# SCH_esp-firework-firing-system-v2_1.net
KiCad netlist of a schematic drawn in EasyEDA
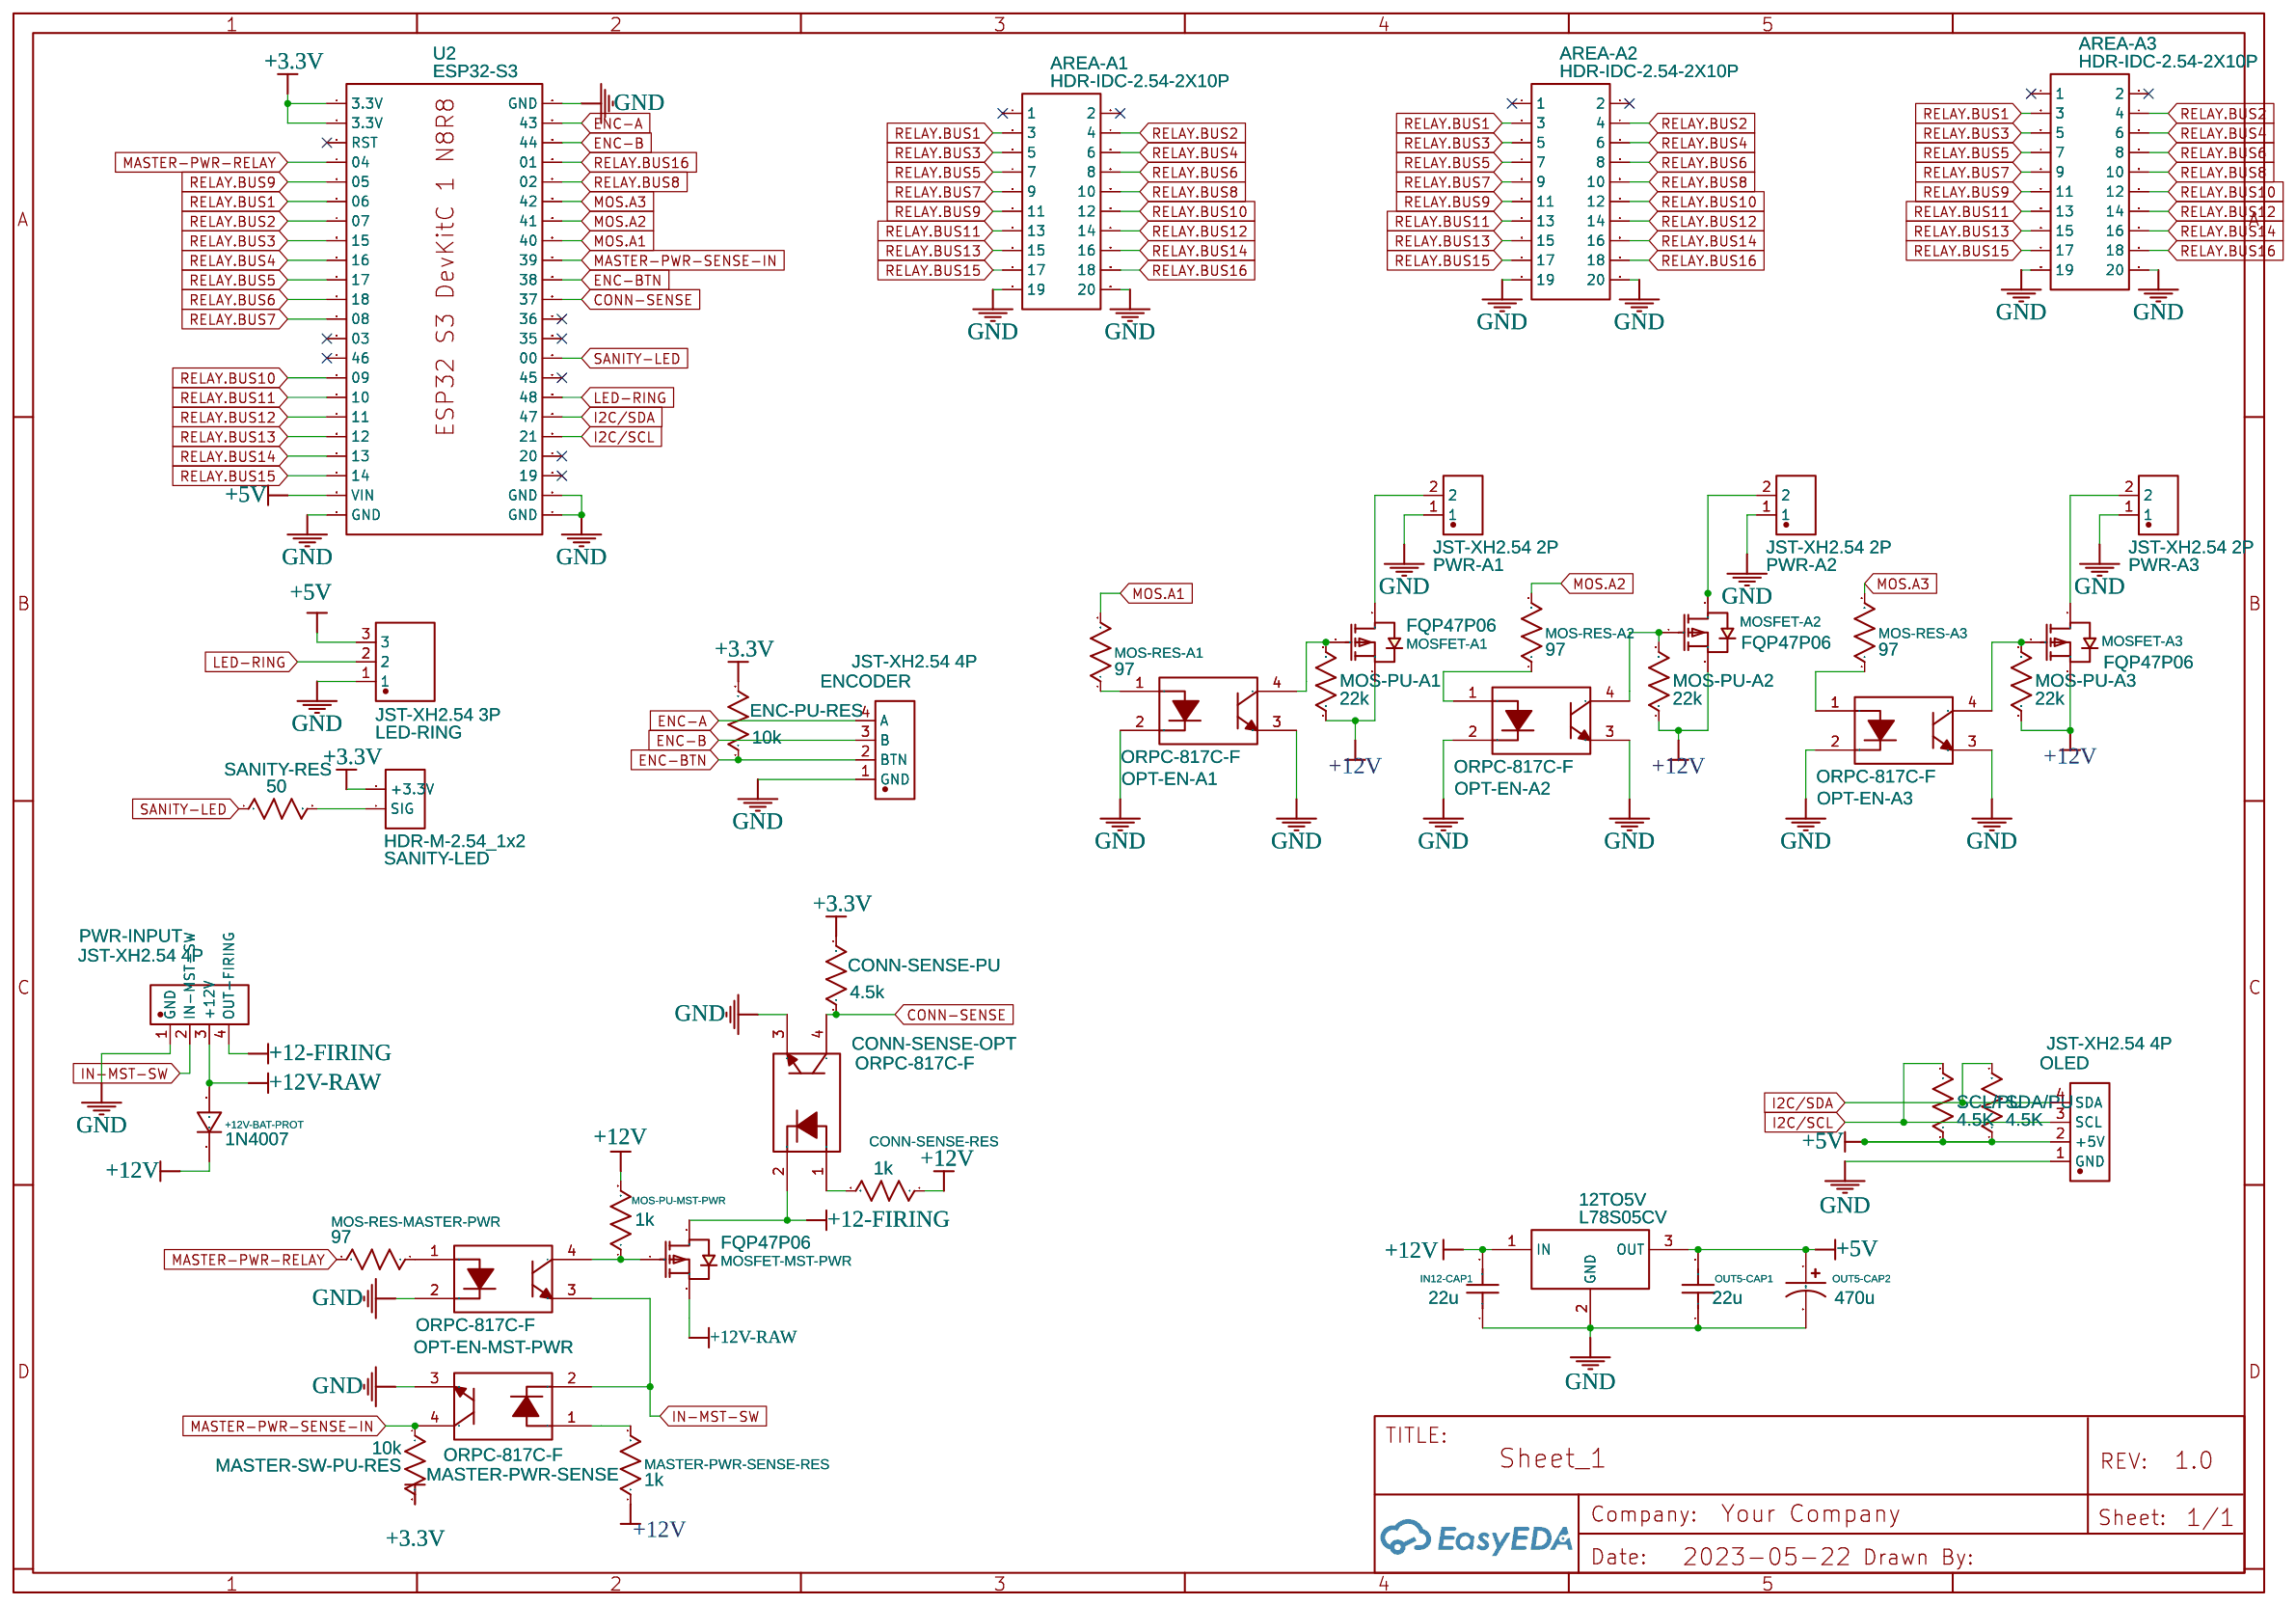
[diagram p0: schematic sheet]

(export (version "E")
  (design (tool "Eeschema 10.0.6"))
  (components
    (comp (ref "+12V-BAT-PROT")
      (value "1N4007")
      (fields (field (name "BOM_Supplier Part") "C106903"))
      (libsource (lib "") (part "1N4007"))
    )
    (comp (ref "12TO5V")
      (value "L78S05CV")
      (fields (field (name "BOM_Supplier Part") "C33043"))
      (libsource (lib "") (part "L78S05CV"))
    )
    (comp (ref "AREA-A1")
      (value "HDR-IDC-2.54-2X10P")
      (fields
        (field (name "BOM_Manufacturer Part") "IDC Box 2.54mm 2X10P　Straight")
        (field (name "BOM_Supplier Part") "C3405")
      )
      (libsource (lib "") (part "HDR-IDC-2.54-2X10P"))
    )
    (comp (ref "AREA-A2")
      (value "HDR-IDC-2.54-2X10P")
      (fields
        (field (name "BOM_Manufacturer Part") "IDC Box 2.54mm 2X10P　Straight")
        (field (name "BOM_Supplier Part") "C3405")
      )
      (libsource (lib "") (part "HDR-IDC-2.54-2X10P"))
    )
    (comp (ref "AREA-A3")
      (value "HDR-IDC-2.54-2X10P")
      (fields
        (field (name "BOM_Manufacturer Part") "IDC Box 2.54mm 2X10P　Straight")
        (field (name "BOM_Supplier Part") "C3405")
      )
      (libsource (lib "") (part "HDR-IDC-2.54-2X10P"))
    )
    (comp (ref "CONN-SENSE-OPT")
      (value "ORPC-817C-F")
      (fields (field (name "BOM_Supplier Part") "C2842770"))
      (libsource (lib "") (part "ORPC-817C-F_3"))
    )
    (comp (ref "CONN-SENSE-PU") (value "4.5k") (libsource (lib "") (part "R_AXIAL-0.3_US_6")))
    (comp (ref "CONN-SENSE-RES") (value "1k") (libsource (lib "") (part "R_AXIAL-0.3_US_11")))
    (comp (ref "ENC-PU-RES") (value "10k") (libsource (lib "") (part "R_AXIAL-0.3_US_1")))
    (comp (ref "ENCODER") (value "JST-XH2.54 4P") (libsource (lib "") (part "JST-XH2.54 4P")))
    (comp (ref "IN12-CAP1") (value "22u") (libsource (lib "") (part "C_RAD-0.1_US_1")))
    (comp (ref "LED-RING") (value "JST-XH2.54 3P") (libsource (lib "") (part "JST-XH2.54 3P")))
    (comp (ref "MASTER-PWR-SENSE")
      (value "ORPC-817C-F")
      (fields (field (name "BOM_Supplier Part") "C2842770"))
      (libsource (lib "") (part "ORPC-817C-F_2"))
    )
    (comp (ref "MASTER-PWR-SENSE-RES") (value "1k") (libsource (lib "") (part "R_AXIAL-0.3_US_7")))
    (comp (ref "MASTER-SW-PU-RES") (value "10k") (libsource (lib "") (part "R_AXIAL-0.3_US_4")))
    (comp (ref "MOS-PU-A1") (value "22k") (libsource (lib "") (part "R_AXIAL-0.3_US_2")))
    (comp (ref "MOS-PU-A2") (value "22k") (libsource (lib "") (part "R_AXIAL-0.3_US_2")))
    (comp (ref "MOS-PU-A3") (value "22k") (libsource (lib "") (part "R_AXIAL-0.3_US_2")))
    (comp (ref "MOS-PU-MST-PWR") (value "1k") (libsource (lib "") (part "R_AXIAL-0.3_US_5")))
    (comp (ref "MOS-RES-A1") (value "97") (libsource (lib "") (part "R_AXIAL-0.3_US")))
    (comp (ref "MOS-RES-A2") (value "97") (libsource (lib "") (part "R_AXIAL-0.3_US")))
    (comp (ref "MOS-RES-A3") (value "97") (libsource (lib "") (part "R_AXIAL-0.3_US")))
    (comp (ref "MOS-RES-MASTER-PWR") (value "97") (libsource (lib "") (part "R_AXIAL-0.3_US_10")))
    (comp (ref "MOSFET-A1")
      (value "FQP47P06")
      (fields (field (name "BOM_Supplier Part") "C462765"))
      (libsource (lib "") (part "FQP47P06"))
    )
    (comp (ref "MOSFET-A2")
      (value "FQP47P06")
      (fields (field (name "BOM_Supplier Part") "C462765"))
      (libsource (lib "") (part "FQP47P06"))
    )
    (comp (ref "MOSFET-A3")
      (value "FQP47P06")
      (fields (field (name "BOM_Supplier Part") "C462765"))
      (libsource (lib "") (part "FQP47P06"))
    )
    (comp (ref "MOSFET-MST-PWR")
      (value "FQP47P06")
      (fields (field (name "BOM_Supplier Part") "C462765"))
      (libsource (lib "") (part "FQP47P06_1"))
    )
    (comp (ref "OLED") (value "JST-XH2.54 4P") (libsource (lib "") (part "JST-XH2.54 4P_1")))
    (comp (ref "OPT-EN-A1")
      (value "ORPC-817C-F")
      (fields (field (name "BOM_Supplier Part") "C2842770"))
      (libsource (lib "") (part "ORPC-817C-F"))
    )
    (comp (ref "OPT-EN-A2")
      (value "ORPC-817C-F")
      (fields (field (name "BOM_Supplier Part") "C2842770"))
      (libsource (lib "") (part "ORPC-817C-F"))
    )
    (comp (ref "OPT-EN-A3")
      (value "ORPC-817C-F")
      (fields (field (name "BOM_Supplier Part") "C2842770"))
      (libsource (lib "") (part "ORPC-817C-F"))
    )
    (comp (ref "OPT-EN-MST-PWR")
      (value "ORPC-817C-F")
      (fields (field (name "BOM_Supplier Part") "C2842770"))
      (libsource (lib "") (part "ORPC-817C-F_1"))
    )
    (comp (ref "OUT5-CAP1") (value "22u") (libsource (lib "") (part "C_RAD-0.1_US")))
    (comp (ref "OUT5-CAP2") (value "470u") (libsource (lib "") (part "CE_TH_D6.3×F2.5_US")))
    (comp (ref "PWR-A1") (value "JST-XH2.54 2P") (libsource (lib "") (part "JST-XH2.54 2P")))
    (comp (ref "PWR-A2") (value "JST-XH2.54 2P") (libsource (lib "") (part "JST-XH2.54 2P")))
    (comp (ref "PWR-A3") (value "JST-XH2.54 2P") (libsource (lib "") (part "JST-XH2.54 2P")))
    (comp (ref "PWR-INPUT") (value "JST-XH2.54 4P") (libsource (lib "") (part "JST-XH2.54 4P_2")))
    (comp (ref "SANITY-LED")
      (value "HDR-M-2.54_1x2")
      (fields (field (name "BOM_Supplier Part") "C124375"))
      (libsource (lib "") (part "HDR-M-2.54_1x2"))
    )
    (comp (ref "SANITY-RES") (value "50") (libsource (lib "") (part "R_AXIAL-0.3_US_9")))
    (comp (ref "SCL/PU") (value "4.5K") (libsource (lib "") (part "R_AXIAL-0.3_US_8")))
    (comp (ref "SDA/PU") (value "4.5K") (libsource (lib "") (part "R_AXIAL-0.3_US_3")))
    (comp (ref "U2") (value "ESP32-S3") (libsource (lib "") (part "ESP32-S3")))
  )
  (nets
    (net (code "1") (name "+3.3V") (class "Default")
      (node (ref "CONN-SENSE-PU") (pin "2") (pinfunction "2_2") (pintype "unspecified"))
      (node (ref "ENC-PU-RES") (pin "2") (pinfunction "2_2") (pintype "unspecified"))
      (node (ref "MASTER-SW-PU-RES") (pin "2") (pinfunction "2_2") (pintype "unspecified"))
      (node (ref "SANITY-LED") (pin "2") (pinfunction "+3.3V_2") (pintype "unspecified"))
      (node (ref "U2") (pin "1") (pinfunction "3.3V_1") (pintype "unspecified"))
      (node (ref "U2") (pin "2") (pinfunction "3.3V_2") (pintype "unspecified"))
    )
    (net (code "2") (name "+5V") (class "Default")
      (node (ref "12TO5V") (pin "3") (pinfunction "OUT_3") (pintype "passive"))
      (node (ref "LED-RING") (pin "3") (pinfunction "3_3") (pintype "unspecified"))
      (node (ref "OLED") (pin "2") (pinfunction "+5V_2") (pintype "unspecified"))
      (node (ref "OUT5-CAP1") (pin "2") (pinfunction "2_2") (pintype "unspecified"))
      (node (ref "OUT5-CAP2") (pin "1") (pinfunction "1_1") (pintype "unspecified"))
      (node (ref "SCL/PU") (pin "1") (pinfunction "1_1") (pintype "unspecified"))
      (node (ref "SDA/PU") (pin "1") (pinfunction "1_1") (pintype "unspecified"))
      (node (ref "U2") (pin "21") (pinfunction "VIN_21") (pintype "unspecified"))
    )
    (net (code "3") (name "+12-FIRING") (class "Default")
      (node (ref "CONN-SENSE-OPT") (pin "2") (pinfunction "2_2") (pintype "unspecified"))
      (node (ref "MOSFET-MST-PWR") (pin "2") (pinfunction "D_2") (pintype "unspecified"))
      (node (ref "PWR-INPUT") (pin "4") (pinfunction "OUT-FIRING_4") (pintype "unspecified"))
    )
    (net (code "4") (name "+12V") (class "Default")
      (node (ref "+12V-BAT-PROT") (pin "1") (pinfunction "1_1") (pintype "unspecified"))
      (node (ref "12TO5V") (pin "1") (pinfunction "IN_1") (pintype "passive"))
      (node (ref "CONN-SENSE-RES") (pin "1") (pinfunction "1_1") (pintype "unspecified"))
      (node (ref "IN12-CAP1") (pin "2") (pinfunction "2_2") (pintype "unspecified"))
      (node (ref "MASTER-PWR-SENSE-RES") (pin "1") (pinfunction "1_1") (pintype "unspecified"))
      (node (ref "MOS-PU-A1") (pin "1") (pinfunction "1_1") (pintype "unspecified"))
      (node (ref "MOS-PU-A2") (pin "1") (pinfunction "1_1") (pintype "unspecified"))
      (node (ref "MOS-PU-A3") (pin "1") (pinfunction "1_1") (pintype "unspecified"))
      (node (ref "MOS-PU-MST-PWR") (pin "2") (pinfunction "2_2") (pintype "unspecified"))
      (node (ref "MOSFET-A1") (pin "3") (pinfunction "S_3") (pintype "unspecified"))
      (node (ref "MOSFET-A2") (pin "3") (pinfunction "S_3") (pintype "unspecified"))
      (node (ref "MOSFET-A3") (pin "3") (pinfunction "S_3") (pintype "unspecified"))
    )
    (net (code "5") (name "+12V-RAW") (class "Default")
      (node (ref "+12V-BAT-PROT") (pin "2") (pinfunction "2_2") (pintype "unspecified"))
      (node (ref "MOSFET-MST-PWR") (pin "3") (pinfunction "S_3") (pintype "unspecified"))
      (node (ref "PWR-INPUT") (pin "3") (pinfunction "+12V_3") (pintype "unspecified"))
    )
    (net (code "6") (name "CONN-SENSE") (class "Default")
      (node (ref "CONN-SENSE-OPT") (pin "4") (pinfunction "4_4") (pintype "unspecified"))
      (node (ref "CONN-SENSE-PU") (pin "1") (pinfunction "1_1") (pintype "unspecified"))
      (node (ref "U2") (pin "33") (pinfunction "37_33") (pintype "unspecified"))
    )
    (net (code "7") (name "ENC-A") (class "Default")
      (node (ref "ENCODER") (pin "4") (pinfunction "A_4") (pintype "unspecified"))
      (node (ref "U2") (pin "24") (pinfunction "43_24") (pintype "unspecified"))
    )
    (net (code "8") (name "ENC-B") (class "Default")
      (node (ref "ENCODER") (pin "3") (pinfunction "B_3") (pintype "unspecified"))
      (node (ref "U2") (pin "25") (pinfunction "44_25") (pintype "unspecified"))
    )
    (net (code "9") (name "ENC-BTN") (class "Default")
      (node (ref "ENC-PU-RES") (pin "1") (pinfunction "1_1") (pintype "unspecified"))
      (node (ref "ENCODER") (pin "2") (pinfunction "BTN_2") (pintype "unspecified"))
      (node (ref "U2") (pin "32") (pinfunction "38_32") (pintype "unspecified"))
    )
    (net (code "10") (name "GND") (class "Default")
      (node (ref "12TO5V") (pin "2") (pinfunction "GND_2") (pintype "passive"))
      (node (ref "AREA-A1") (pin "19") (pinfunction "19_19") (pintype "unspecified"))
      (node (ref "AREA-A1") (pin "20") (pinfunction "20_20") (pintype "unspecified"))
      (node (ref "AREA-A2") (pin "19") (pinfunction "19_19") (pintype "unspecified"))
      (node (ref "AREA-A2") (pin "20") (pinfunction "20_20") (pintype "unspecified"))
      (node (ref "AREA-A3") (pin "19") (pinfunction "19_19") (pintype "unspecified"))
      (node (ref "AREA-A3") (pin "20") (pinfunction "20_20") (pintype "unspecified"))
      (node (ref "CONN-SENSE-OPT") (pin "3") (pinfunction "3_3") (pintype "unspecified"))
      (node (ref "ENCODER") (pin "1") (pinfunction "GND_1") (pintype "unspecified"))
      (node (ref "IN12-CAP1") (pin "1") (pinfunction "1_1") (pintype "unspecified"))
      (node (ref "LED-RING") (pin "1") (pinfunction "1_1") (pintype "unspecified"))
      (node (ref "MASTER-PWR-SENSE") (pin "3") (pinfunction "3_3") (pintype "unspecified"))
      (node (ref "OLED") (pin "1") (pinfunction "GND_1") (pintype "unspecified"))
      (node (ref "OPT-EN-A1") (pin "2") (pinfunction "2_2") (pintype "unspecified"))
      (node (ref "OPT-EN-A1") (pin "3") (pinfunction "3_3") (pintype "unspecified"))
      (node (ref "OPT-EN-A2") (pin "2") (pinfunction "2_2") (pintype "unspecified"))
      (node (ref "OPT-EN-A2") (pin "3") (pinfunction "3_3") (pintype "unspecified"))
      (node (ref "OPT-EN-A3") (pin "2") (pinfunction "2_2") (pintype "unspecified"))
      (node (ref "OPT-EN-A3") (pin "3") (pinfunction "3_3") (pintype "unspecified"))
      (node (ref "OPT-EN-MST-PWR") (pin "2") (pinfunction "2_2") (pintype "unspecified"))
      (node (ref "OUT5-CAP1") (pin "1") (pinfunction "1_1") (pintype "unspecified"))
      (node (ref "OUT5-CAP2") (pin "2") (pinfunction "2_2") (pintype "unspecified"))
      (node (ref "PWR-A1") (pin "1") (pinfunction "1_1") (pintype "unspecified"))
      (node (ref "PWR-A2") (pin "1") (pinfunction "1_1") (pintype "unspecified"))
      (node (ref "PWR-A3") (pin "1") (pinfunction "1_1") (pintype "unspecified"))
      (node (ref "PWR-INPUT") (pin "1") (pinfunction "GND_1") (pintype "unspecified"))
      (node (ref "U2") (pin "22") (pinfunction "GND_22") (pintype "unspecified"))
      (node (ref "U2") (pin "23") (pinfunction "GND_23") (pintype "unspecified"))
      (node (ref "U2") (pin "43") (pinfunction "GND_43") (pintype "unspecified"))
      (node (ref "U2") (pin "44") (pinfunction "GND_44") (pintype "unspecified"))
    )
    (net (code "11") (name "I2C{slash}SCL") (class "Default")
      (node (ref "OLED") (pin "3") (pinfunction "SCL_3") (pintype "unspecified"))
      (node (ref "SCL/PU") (pin "2") (pinfunction "2_2") (pintype "unspecified"))
      (node (ref "U2") (pin "40") (pinfunction "21_40") (pintype "unspecified"))
    )
    (net (code "12") (name "I2C{slash}SDA") (class "Default")
      (node (ref "OLED") (pin "4") (pinfunction "SDA_4") (pintype "unspecified"))
      (node (ref "SDA/PU") (pin "2") (pinfunction "2_2") (pintype "unspecified"))
      (node (ref "U2") (pin "39") (pinfunction "47_39") (pintype "unspecified"))
    )
    (net (code "13") (name "IN-MST-SW") (class "Default")
      (node (ref "MASTER-PWR-SENSE") (pin "2") (pinfunction "2_2") (pintype "unspecified"))
      (node (ref "OPT-EN-MST-PWR") (pin "3") (pinfunction "3_3") (pintype "unspecified"))
      (node (ref "PWR-INPUT") (pin "2") (pinfunction "IN-MST-SW_2") (pintype "unspecified"))
    )
    (net (code "14") (name "LED-RING") (class "Default")
      (node (ref "LED-RING") (pin "2") (pinfunction "2_2") (pintype "unspecified"))
      (node (ref "U2") (pin "38") (pinfunction "48_38") (pintype "unspecified"))
    )
    (net (code "15") (name "MASTER-PWR-RELAY") (class "Default")
      (node (ref "MOS-RES-MASTER-PWR") (pin "2") (pinfunction "2_2") (pintype "unspecified"))
      (node (ref "U2") (pin "4") (pinfunction "04_4") (pintype "unspecified"))
    )
    (net (code "16") (name "MASTER-PWR-SENSE-IN") (class "Default")
      (node (ref "MASTER-PWR-SENSE") (pin "4") (pinfunction "4_4") (pintype "unspecified"))
      (node (ref "MASTER-SW-PU-RES") (pin "1") (pinfunction "1_1") (pintype "unspecified"))
      (node (ref "U2") (pin "31") (pinfunction "39_31") (pintype "unspecified"))
    )
    (net (code "17") (name "MOS.A1") (class "Default")
      (node (ref "MOS-RES-A1") (pin "2") (pinfunction "2_2") (pintype "unspecified"))
      (node (ref "U2") (pin "30") (pinfunction "40_30") (pintype "unspecified"))
    )
    (net (code "18") (name "MOS.A2") (class "Default")
      (node (ref "MOS-RES-A2") (pin "2") (pinfunction "2_2") (pintype "unspecified"))
      (node (ref "U2") (pin "29") (pinfunction "41_29") (pintype "unspecified"))
    )
    (net (code "19") (name "MOS.A3") (class "Default")
      (node (ref "MOS-RES-A3") (pin "2") (pinfunction "2_2") (pintype "unspecified"))
      (node (ref "U2") (pin "28") (pinfunction "42_28") (pintype "unspecified"))
    )
    (net (code "20") (name "Net-(CONN-SENSE-OPT-Pad1)") (class "Default")
      (node (ref "CONN-SENSE-OPT") (pin "1") (pinfunction "1_1") (pintype "unspecified"))
      (node (ref "CONN-SENSE-RES") (pin "2") (pinfunction "2_2") (pintype "unspecified"))
    )
    (net (code "21") (name "Net-(MASTER-PWR-SENSE-Pad1)") (class "Default")
      (node (ref "MASTER-PWR-SENSE") (pin "1") (pinfunction "1_1") (pintype "unspecified"))
      (node (ref "MASTER-PWR-SENSE-RES") (pin "2") (pinfunction "2_2") (pintype "unspecified"))
    )
    (net (code "22") (name "Net-(MOS-RES-A1-Pad1)") (class "Default")
      (node (ref "MOS-RES-A1") (pin "1") (pinfunction "1_1") (pintype "unspecified"))
      (node (ref "OPT-EN-A1") (pin "1") (pinfunction "1_1") (pintype "unspecified"))
    )
    (net (code "23") (name "Net-(MOS-RES-A2-Pad1)") (class "Default")
      (node (ref "MOS-RES-A2") (pin "1") (pinfunction "1_1") (pintype "unspecified"))
      (node (ref "OPT-EN-A2") (pin "1") (pinfunction "1_1") (pintype "unspecified"))
    )
    (net (code "24") (name "Net-(MOS-RES-A3-Pad1)") (class "Default")
      (node (ref "MOS-RES-A3") (pin "1") (pinfunction "1_1") (pintype "unspecified"))
      (node (ref "OPT-EN-A3") (pin "1") (pinfunction "1_1") (pintype "unspecified"))
    )
    (net (code "25") (name "Net-(MOS-RES-MASTER-PWR-Pad1)") (class "Default")
      (node (ref "MOS-RES-MASTER-PWR") (pin "1") (pinfunction "1_1") (pintype "unspecified"))
      (node (ref "OPT-EN-MST-PWR") (pin "1") (pinfunction "1_1") (pintype "unspecified"))
    )
    (net (code "26") (name "Net-(MOSFET-A1-D)") (class "Default")
      (node (ref "MOSFET-A1") (pin "2") (pinfunction "D_2") (pintype "unspecified"))
      (node (ref "PWR-A1") (pin "2") (pinfunction "2_2") (pintype "unspecified"))
    )
    (net (code "27") (name "Net-(MOSFET-A1-G)") (class "Default")
      (node (ref "MOS-PU-A1") (pin "2") (pinfunction "2_2") (pintype "unspecified"))
      (node (ref "MOSFET-A1") (pin "1") (pinfunction "G_1") (pintype "unspecified"))
      (node (ref "OPT-EN-A1") (pin "4") (pinfunction "4_4") (pintype "unspecified"))
    )
    (net (code "28") (name "Net-(MOSFET-A2-D)") (class "Default")
      (node (ref "MOSFET-A2") (pin "2") (pinfunction "D_2") (pintype "unspecified"))
      (node (ref "PWR-A2") (pin "2") (pinfunction "2_2") (pintype "unspecified"))
    )
    (net (code "29") (name "Net-(MOSFET-A2-G)") (class "Default")
      (node (ref "MOS-PU-A2") (pin "2") (pinfunction "2_2") (pintype "unspecified"))
      (node (ref "MOSFET-A2") (pin "1") (pinfunction "G_1") (pintype "unspecified"))
      (node (ref "OPT-EN-A2") (pin "4") (pinfunction "4_4") (pintype "unspecified"))
    )
    (net (code "30") (name "Net-(MOSFET-A3-D)") (class "Default")
      (node (ref "MOSFET-A3") (pin "2") (pinfunction "D_2") (pintype "unspecified"))
      (node (ref "PWR-A3") (pin "2") (pinfunction "2_2") (pintype "unspecified"))
    )
    (net (code "31") (name "Net-(MOSFET-A3-G)") (class "Default")
      (node (ref "MOS-PU-A3") (pin "2") (pinfunction "2_2") (pintype "unspecified"))
      (node (ref "MOSFET-A3") (pin "1") (pinfunction "G_1") (pintype "unspecified"))
      (node (ref "OPT-EN-A3") (pin "4") (pinfunction "4_4") (pintype "unspecified"))
    )
    (net (code "32") (name "Net-(MOSFET-MST-PWR-G)") (class "Default")
      (node (ref "MOS-PU-MST-PWR") (pin "1") (pinfunction "1_1") (pintype "unspecified"))
      (node (ref "MOSFET-MST-PWR") (pin "1") (pinfunction "G_1") (pintype "unspecified"))
      (node (ref "OPT-EN-MST-PWR") (pin "4") (pinfunction "4_4") (pintype "unspecified"))
    )
    (net (code "33") (name "Net-(SANITY-LED-SIG)") (class "Default")
      (node (ref "SANITY-LED") (pin "1") (pinfunction "SIG_1") (pintype "unspecified"))
      (node (ref "SANITY-RES") (pin "2") (pinfunction "2_2") (pintype "unspecified"))
    )
    (net (code "34") (name "RELAY.BUS1") (class "Default")
      (node (ref "AREA-A1") (pin "3") (pinfunction "3_3") (pintype "unspecified"))
      (node (ref "AREA-A2") (pin "3") (pinfunction "3_3") (pintype "unspecified"))
      (node (ref "AREA-A3") (pin "3") (pinfunction "3_3") (pintype "unspecified"))
      (node (ref "U2") (pin "6") (pinfunction "06_6") (pintype "unspecified"))
    )
    (net (code "35") (name "RELAY.BUS2") (class "Default")
      (node (ref "AREA-A1") (pin "4") (pinfunction "4_4") (pintype "unspecified"))
      (node (ref "AREA-A2") (pin "4") (pinfunction "4_4") (pintype "unspecified"))
      (node (ref "AREA-A3") (pin "4") (pinfunction "4_4") (pintype "unspecified"))
      (node (ref "U2") (pin "7") (pinfunction "07_7") (pintype "unspecified"))
    )
    (net (code "36") (name "RELAY.BUS3") (class "Default")
      (node (ref "AREA-A1") (pin "5") (pinfunction "5_5") (pintype "unspecified"))
      (node (ref "AREA-A2") (pin "5") (pinfunction "5_5") (pintype "unspecified"))
      (node (ref "AREA-A3") (pin "5") (pinfunction "5_5") (pintype "unspecified"))
      (node (ref "U2") (pin "8") (pinfunction "15_8") (pintype "unspecified"))
    )
    (net (code "37") (name "RELAY.BUS4") (class "Default")
      (node (ref "AREA-A1") (pin "6") (pinfunction "6_6") (pintype "unspecified"))
      (node (ref "AREA-A2") (pin "6") (pinfunction "6_6") (pintype "unspecified"))
      (node (ref "AREA-A3") (pin "6") (pinfunction "6_6") (pintype "unspecified"))
      (node (ref "U2") (pin "9") (pinfunction "16_9") (pintype "unspecified"))
    )
    (net (code "38") (name "RELAY.BUS5") (class "Default")
      (node (ref "AREA-A1") (pin "7") (pinfunction "7_7") (pintype "unspecified"))
      (node (ref "AREA-A2") (pin "7") (pinfunction "7_7") (pintype "unspecified"))
      (node (ref "AREA-A3") (pin "7") (pinfunction "7_7") (pintype "unspecified"))
      (node (ref "U2") (pin "10") (pinfunction "17_10") (pintype "unspecified"))
    )
    (net (code "39") (name "RELAY.BUS6") (class "Default")
      (node (ref "AREA-A1") (pin "8") (pinfunction "8_8") (pintype "unspecified"))
      (node (ref "AREA-A2") (pin "8") (pinfunction "8_8") (pintype "unspecified"))
      (node (ref "AREA-A3") (pin "8") (pinfunction "8_8") (pintype "unspecified"))
      (node (ref "U2") (pin "11") (pinfunction "18_11") (pintype "unspecified"))
    )
    (net (code "40") (name "RELAY.BUS7") (class "Default")
      (node (ref "AREA-A1") (pin "9") (pinfunction "9_9") (pintype "unspecified"))
      (node (ref "AREA-A2") (pin "9") (pinfunction "9_9") (pintype "unspecified"))
      (node (ref "AREA-A3") (pin "9") (pinfunction "9_9") (pintype "unspecified"))
      (node (ref "U2") (pin "12") (pinfunction "08_12") (pintype "unspecified"))
    )
    (net (code "41") (name "RELAY.BUS8") (class "Default")
      (node (ref "AREA-A1") (pin "10") (pinfunction "10_10") (pintype "unspecified"))
      (node (ref "AREA-A2") (pin "10") (pinfunction "10_10") (pintype "unspecified"))
      (node (ref "AREA-A3") (pin "10") (pinfunction "10_10") (pintype "unspecified"))
      (node (ref "U2") (pin "27") (pinfunction "02_27") (pintype "unspecified"))
    )
    (net (code "42") (name "RELAY.BUS9") (class "Default")
      (node (ref "AREA-A1") (pin "11") (pinfunction "11_11") (pintype "unspecified"))
      (node (ref "AREA-A2") (pin "11") (pinfunction "11_11") (pintype "unspecified"))
      (node (ref "AREA-A3") (pin "11") (pinfunction "11_11") (pintype "unspecified"))
      (node (ref "U2") (pin "5") (pinfunction "05_5") (pintype "unspecified"))
    )
    (net (code "43") (name "RELAY.BUS10") (class "Default")
      (node (ref "AREA-A1") (pin "12") (pinfunction "12_12") (pintype "unspecified"))
      (node (ref "AREA-A2") (pin "12") (pinfunction "12_12") (pintype "unspecified"))
      (node (ref "AREA-A3") (pin "12") (pinfunction "12_12") (pintype "unspecified"))
      (node (ref "U2") (pin "15") (pinfunction "09_15") (pintype "unspecified"))
    )
    (net (code "44") (name "RELAY.BUS11") (class "Default")
      (node (ref "AREA-A1") (pin "13") (pinfunction "13_13") (pintype "unspecified"))
      (node (ref "AREA-A2") (pin "13") (pinfunction "13_13") (pintype "unspecified"))
      (node (ref "AREA-A3") (pin "13") (pinfunction "13_13") (pintype "unspecified"))
      (node (ref "U2") (pin "16") (pinfunction "10_16") (pintype "unspecified"))
    )
    (net (code "45") (name "RELAY.BUS12") (class "Default")
      (node (ref "AREA-A1") (pin "14") (pinfunction "14_14") (pintype "unspecified"))
      (node (ref "AREA-A2") (pin "14") (pinfunction "14_14") (pintype "unspecified"))
      (node (ref "AREA-A3") (pin "14") (pinfunction "14_14") (pintype "unspecified"))
      (node (ref "U2") (pin "17") (pinfunction "11_17") (pintype "unspecified"))
    )
    (net (code "46") (name "RELAY.BUS13") (class "Default")
      (node (ref "AREA-A1") (pin "15") (pinfunction "15_15") (pintype "unspecified"))
      (node (ref "AREA-A2") (pin "15") (pinfunction "15_15") (pintype "unspecified"))
      (node (ref "AREA-A3") (pin "15") (pinfunction "15_15") (pintype "unspecified"))
      (node (ref "U2") (pin "18") (pinfunction "12_18") (pintype "unspecified"))
    )
    (net (code "47") (name "RELAY.BUS14") (class "Default")
      (node (ref "AREA-A1") (pin "16") (pinfunction "16_16") (pintype "unspecified"))
      (node (ref "AREA-A2") (pin "16") (pinfunction "16_16") (pintype "unspecified"))
      (node (ref "AREA-A3") (pin "16") (pinfunction "16_16") (pintype "unspecified"))
      (node (ref "U2") (pin "19") (pinfunction "13_19") (pintype "unspecified"))
    )
    (net (code "48") (name "RELAY.BUS15") (class "Default")
      (node (ref "AREA-A1") (pin "17") (pinfunction "17_17") (pintype "unspecified"))
      (node (ref "AREA-A2") (pin "17") (pinfunction "17_17") (pintype "unspecified"))
      (node (ref "AREA-A3") (pin "17") (pinfunction "17_17") (pintype "unspecified"))
      (node (ref "U2") (pin "20") (pinfunction "14_20") (pintype "unspecified"))
    )
    (net (code "49") (name "RELAY.BUS16") (class "Default")
      (node (ref "AREA-A1") (pin "18") (pinfunction "18_18") (pintype "unspecified"))
      (node (ref "AREA-A2") (pin "18") (pinfunction "18_18") (pintype "unspecified"))
      (node (ref "AREA-A3") (pin "18") (pinfunction "18_18") (pintype "unspecified"))
      (node (ref "U2") (pin "26") (pinfunction "01_26") (pintype "unspecified"))
    )
    (net (code "50") (name "SANITY-LED") (class "Default")
      (node (ref "SANITY-RES") (pin "1") (pinfunction "1_1") (pintype "unspecified"))
      (node (ref "U2") (pin "36") (pinfunction "00_36") (pintype "unspecified"))
    )
    (net (code "51") (name "unconnected-(AREA-A1-Pad1)") (class "Default")
      (node (ref "AREA-A1") (pin "1") (pinfunction "1_1") (pintype "unspecified+no_connect"))
    )
    (net (code "52") (name "unconnected-(AREA-A1-Pad2)") (class "Default")
      (node (ref "AREA-A1") (pin "2") (pinfunction "2_2") (pintype "unspecified+no_connect"))
    )
    (net (code "53") (name "unconnected-(AREA-A2-Pad1)") (class "Default")
      (node (ref "AREA-A2") (pin "1") (pinfunction "1_1") (pintype "unspecified+no_connect"))
    )
    (net (code "54") (name "unconnected-(AREA-A2-Pad2)") (class "Default")
      (node (ref "AREA-A2") (pin "2") (pinfunction "2_2") (pintype "unspecified+no_connect"))
    )
    (net (code "55") (name "unconnected-(AREA-A3-Pad1)") (class "Default")
      (node (ref "AREA-A3") (pin "1") (pinfunction "1_1") (pintype "unspecified+no_connect"))
    )
    (net (code "56") (name "unconnected-(AREA-A3-Pad2)") (class "Default")
      (node (ref "AREA-A3") (pin "2") (pinfunction "2_2") (pintype "unspecified+no_connect"))
    )
    (net (code "57") (name "unconnected-(U2-03-Pad13)") (class "Default")
      (node (ref "U2") (pin "13") (pinfunction "03_13") (pintype "unspecified+no_connect"))
    )
    (net (code "58") (name "unconnected-(U2-19-Pad42)") (class "Default")
      (node (ref "U2") (pin "42") (pinfunction "19_42") (pintype "unspecified+no_connect"))
    )
    (net (code "59") (name "unconnected-(U2-20-Pad41)") (class "Default")
      (node (ref "U2") (pin "41") (pinfunction "20_41") (pintype "unspecified+no_connect"))
    )
    (net (code "60") (name "unconnected-(U2-36-Pad34)") (class "Default")
      (node (ref "U2") (pin "34") (pinfunction "36_34") (pintype "unspecified+no_connect"))
    )
    (net (code "61") (name "unconnected-(U2-45-Pad37)") (class "Default")
      (node (ref "U2") (pin "37") (pinfunction "45_37") (pintype "unspecified+no_connect"))
    )
    (net (code "62") (name "unconnected-(U2-46-Pad14)") (class "Default")
      (node (ref "U2") (pin "14") (pinfunction "46_14") (pintype "unspecified+no_connect"))
    )
    (net (code "63") (name "unconnected-(U2-Pad35)") (class "Default")
      (node (ref "U2") (pin "35") (pinfunction "35_35") (pintype "unspecified+no_connect"))
    )
    (net (code "64") (name "unconnected-(U2-RST-Pad3)") (class "Default")
      (node (ref "U2") (pin "3") (pinfunction "RST_3") (pintype "unspecified+no_connect"))
    )
  )
)
